# Thermometers.net
KiCad netlist of a schematic drawn in Altium Designer
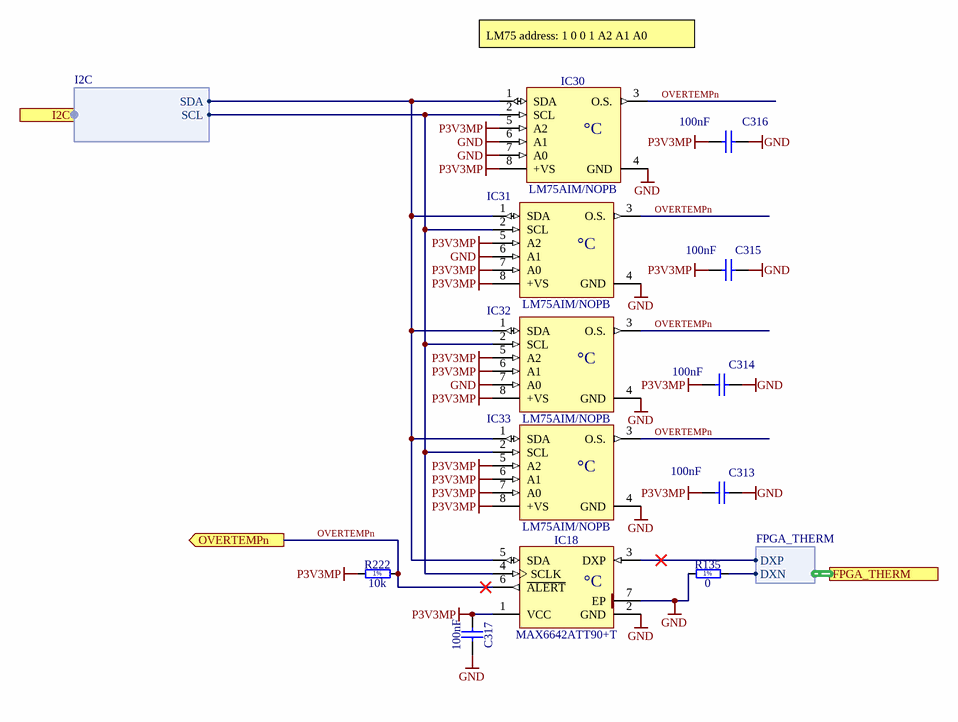
[diagram p0: Thermometers.SchDoc]

(export (version "E")
  (design (tool "Eeschema 10.0.6"))
  (components
    (comp (ref "C313")
      (value "100nF")
      (footprint "CAPC0603X33N")
      (description "Non-polarised capacitor")
      (fields
        (field (name "PART NUMBER") "CC0201_100NF_6.3V_10%_X5R")
        (field (name "VOLTAGE") "6.3V")
        (field (name "AUTHOR") "CERN DEM JLC")
      )
      (libsource (lib "Capacitors") (part "Capacitor - non polarized"))
    )
    (comp (ref "C314")
      (value "100nF")
      (footprint "CAPC0603X33N")
      (description "Non-polarised capacitor")
      (fields
        (field (name "PART NUMBER") "CC0201_100NF_6.3V_10%_X5R")
        (field (name "VOLTAGE") "6.3V")
        (field (name "AUTHOR") "CERN DEM JLC")
      )
      (libsource (lib "Capacitors") (part "Capacitor - non polarized"))
    )
    (comp (ref "C315")
      (value "100nF")
      (footprint "CAPC0603X33N")
      (description "Non-polarised capacitor")
      (fields
        (field (name "PART NUMBER") "CC0201_100NF_6.3V_10%_X5R")
        (field (name "VOLTAGE") "6.3V")
        (field (name "AUTHOR") "CERN DEM JLC")
      )
      (libsource (lib "Capacitors") (part "Capacitor - non polarized"))
    )
    (comp (ref "C316")
      (value "100nF")
      (footprint "CAPC0603X33N")
      (description "Non-polarised capacitor")
      (fields
        (field (name "PART NUMBER") "CC0201_100NF_6.3V_10%_X5R")
        (field (name "VOLTAGE") "6.3V")
        (field (name "AUTHOR") "CERN DEM JLC")
      )
      (libsource (lib "Capacitors") (part "Capacitor - non polarized"))
    )
    (comp (ref "C317")
      (value "100nF")
      (footprint "CAPC0603X33N")
      (description "Non-polarised capacitor")
      (fields
        (field (name "PART NUMBER") "CC0201_100NF_6.3V_10%_X5R")
        (field (name "VOLTAGE") "6.3V")
        (field (name "AUTHOR") "CERN DEM JLC")
      )
      (libsource (lib "Capacitors") (part "Capacitor - non polarized"))
    )
    (comp (ref "IC18")
      (value "MAX6642ATT90+T")
      (footprint "SON95P300X300X80-7N-R160X240")
      (description "±1°C, SMBus-Compatible Remote/Local Temperature Sensor with Overtemperature Alarm")
      (fields (field (name "MANUFACTURER") "MAXIM") (field (name "AUTHOR") "CERN DEM JLC"))
      (libsource (lib "ICs And Semiconductors") (part "MAX6642ATT"))
    )
    (comp (ref "IC30")
      (value "LM75AIM/NOPB")
      (footprint "SOIC127P600X175-8N")
      (description "Digital Temperature Sensor and Thermal Watchdog with Two-Wire Interface")
      (fields (field (name "MANUFACTURER") "TEXAS INSTRUMENTS") (field (name "AUTHOR") "CERN DEM JLC"))
      (libsource (lib "ICs And Semiconductors") (part "LM75"))
    )
    (comp (ref "IC31")
      (value "LM75AIM/NOPB")
      (footprint "SOIC127P600X175-8N")
      (description "Digital Temperature Sensor and Thermal Watchdog with Two-Wire Interface")
      (fields (field (name "MANUFACTURER") "TEXAS INSTRUMENTS") (field (name "AUTHOR") "CERN DEM JLC"))
      (libsource (lib "ICs And Semiconductors") (part "LM75"))
    )
    (comp (ref "IC32")
      (value "LM75AIM/NOPB")
      (footprint "SOIC127P600X175-8N")
      (description "Digital Temperature Sensor and Thermal Watchdog with Two-Wire Interface")
      (fields (field (name "MANUFACTURER") "TEXAS INSTRUMENTS") (field (name "AUTHOR") "CERN DEM JLC"))
      (libsource (lib "ICs And Semiconductors") (part "LM75"))
    )
    (comp (ref "IC33")
      (value "LM75AIM/NOPB")
      (footprint "SOIC127P600X175-8N")
      (description "Digital Temperature Sensor and Thermal Watchdog with Two-Wire Interface")
      (fields (field (name "MANUFACTURER") "TEXAS INSTRUMENTS") (field (name "AUTHOR") "CERN DEM JLC"))
      (libsource (lib "ICs And Semiconductors") (part "LM75"))
    )
    (comp (ref "R135")
      (value "0")
      (footprint "RESC1005X40N")
      (description "Resistor - 1%")
      (fields
        (field (name "PART NUMBER") "R0402_0R_JUMPER")
        (field (name "MANUFACTURER") "GENERIC")
        (field (name "AUTHOR") "CERN DEM JLC")
      )
      (libsource (lib "Resistors") (part "Resistor - 1%"))
    )
    (comp (ref "R222")
      (value "10k")
      (footprint "RESC1005X40N")
      (description "Resistor - 1%")
      (fields
        (field (name "PART NUMBER") "R0402_10K_1%_0.0625W_100PPM")
        (field (name "POWER") "0.0625W")
        (field (name "AUTHOR") "CERN DEM JLC")
      )
      (libsource (lib "Resistors") (part "Resistor - 1%"))
    )
  )
  (nets
    (net (code "3") (name "/DXN") (class "Default")
      (node (ref "R135") (pin "1") (pinfunction "1_1") (pintype "passive"))
    )
    (net (code "4") (name "/DXP") (class "Default")
      (node (ref "IC18") (pin "3") (pinfunction "DXP_3") (pintype "input"))
    )
    (net (code "5") (name "/OVERTEMPn") (class "Default")
      (node (ref "IC18") (pin "6") (pinfunction "~{ALERT}_6") (pintype "output"))
      (node (ref "IC30") (pin "3") (pinfunction "O.S._3") (pintype "output"))
      (node (ref "IC31") (pin "3") (pinfunction "O.S._3") (pintype "output"))
      (node (ref "IC32") (pin "3") (pinfunction "O.S._3") (pintype "output"))
      (node (ref "IC33") (pin "3") (pinfunction "O.S._3") (pintype "output"))
      (node (ref "R222") (pin "2") (pinfunction "2_2") (pintype "passive"))
    )
    (net (code "6") (name "/SCL") (class "Default")
      (node (ref "IC18") (pin "4") (pinfunction "SCLK_4") (pintype "input"))
      (node (ref "IC30") (pin "2") (pinfunction "SCL_2") (pintype "input"))
      (node (ref "IC31") (pin "2") (pinfunction "SCL_2") (pintype "input"))
      (node (ref "IC32") (pin "2") (pinfunction "SCL_2") (pintype "input"))
      (node (ref "IC33") (pin "2") (pinfunction "SCL_2") (pintype "input"))
    )
    (net (code "7") (name "/SDA") (class "Default")
      (node (ref "IC18") (pin "5") (pinfunction "SDA_5") (pintype "bidirectional"))
      (node (ref "IC30") (pin "1") (pinfunction "SDA_1") (pintype "bidirectional"))
      (node (ref "IC31") (pin "1") (pinfunction "SDA_1") (pintype "bidirectional"))
      (node (ref "IC32") (pin "1") (pinfunction "SDA_1") (pintype "bidirectional"))
      (node (ref "IC33") (pin "1") (pinfunction "SDA_1") (pintype "bidirectional"))
    )
    (net (code "10") (name "GND") (class "Default")
      (node (ref "C313") (pin "2") (pinfunction "2_2") (pintype "passive"))
      (node (ref "C314") (pin "2") (pinfunction "2_2") (pintype "passive"))
      (node (ref "C315") (pin "2") (pinfunction "2_2") (pintype "passive"))
      (node (ref "C316") (pin "2") (pinfunction "2_2") (pintype "passive"))
      (node (ref "C317") (pin "2") (pinfunction "2_2") (pintype "passive"))
      (node (ref "IC18") (pin "2") (pinfunction "GND_2") (pintype "power_in"))
      (node (ref "IC18") (pin "7") (pinfunction "EP_7") (pintype "power_in"))
      (node (ref "IC30") (pin "4") (pinfunction "GND_4") (pintype "power_in"))
      (node (ref "IC30") (pin "6") (pinfunction "A1_6") (pintype "input"))
      (node (ref "IC30") (pin "7") (pinfunction "A0_7") (pintype "input"))
      (node (ref "IC31") (pin "4") (pinfunction "GND_4") (pintype "power_in"))
      (node (ref "IC31") (pin "6") (pinfunction "A1_6") (pintype "input"))
      (node (ref "IC32") (pin "4") (pinfunction "GND_4") (pintype "power_in"))
      (node (ref "IC32") (pin "7") (pinfunction "A0_7") (pintype "input"))
      (node (ref "IC33") (pin "4") (pinfunction "GND_4") (pintype "power_in"))
      (node (ref "R135") (pin "2") (pinfunction "2_2") (pintype "passive"))
    )
    (net (code "11") (name "P3V3MP") (class "Default")
      (node (ref "C313") (pin "1") (pinfunction "1_1") (pintype "passive"))
      (node (ref "C314") (pin "1") (pinfunction "1_1") (pintype "passive"))
      (node (ref "C315") (pin "1") (pinfunction "1_1") (pintype "passive"))
      (node (ref "C316") (pin "1") (pinfunction "1_1") (pintype "passive"))
      (node (ref "C317") (pin "1") (pinfunction "1_1") (pintype "passive"))
      (node (ref "IC18") (pin "1") (pinfunction "VCC_1") (pintype "power_in"))
      (node (ref "IC30") (pin "5") (pinfunction "A2_5") (pintype "input"))
      (node (ref "IC30") (pin "8") (pinfunction "+VS_8") (pintype "power_in"))
      (node (ref "IC31") (pin "5") (pinfunction "A2_5") (pintype "input"))
      (node (ref "IC31") (pin "7") (pinfunction "A0_7") (pintype "input"))
      (node (ref "IC31") (pin "8") (pinfunction "+VS_8") (pintype "power_in"))
      (node (ref "IC32") (pin "5") (pinfunction "A2_5") (pintype "input"))
      (node (ref "IC32") (pin "6") (pinfunction "A1_6") (pintype "input"))
      (node (ref "IC32") (pin "8") (pinfunction "+VS_8") (pintype "power_in"))
      (node (ref "IC33") (pin "5") (pinfunction "A2_5") (pintype "input"))
      (node (ref "IC33") (pin "6") (pinfunction "A1_6") (pintype "input"))
      (node (ref "IC33") (pin "7") (pinfunction "A0_7") (pintype "input"))
      (node (ref "IC33") (pin "8") (pinfunction "+VS_8") (pintype "power_in"))
      (node (ref "R222") (pin "1") (pinfunction "1_1") (pintype "passive"))
    )
  )
)
